# WX_sat_filter.net
KiCad netlist of a schematic drawn in Altium Designer
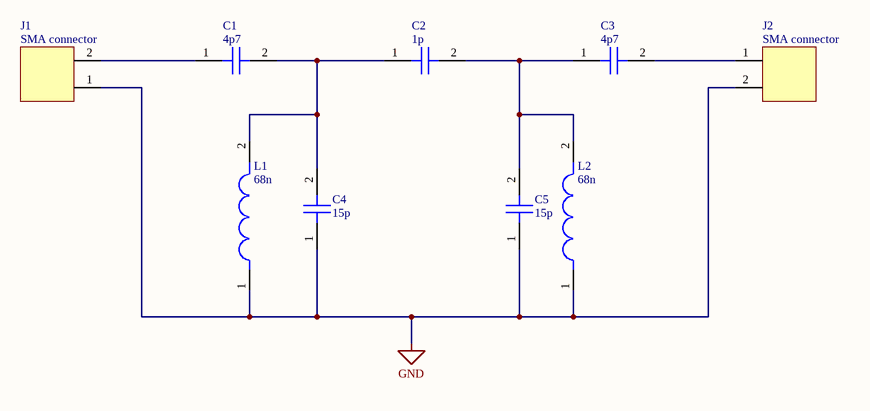
[diagram p0: WX sat filter.SchDoc]

(export (version "E")
  (design (tool "Eeschema 10.0.6"))
  (components
    (comp (ref "C1")
      (value "4p7")
      (footprint "0603_CAP")
      (libsource (lib "Radolovic_SCH_Library") (part "CAP_0603_generic"))
    )
    (comp (ref "C2")
      (value "1p")
      (footprint "0603_CAP")
      (libsource (lib "Radolovic_SCH_Library") (part "CAP_0603_generic"))
    )
    (comp (ref "C3")
      (value "4p7")
      (footprint "0603_CAP")
      (libsource (lib "Radolovic_SCH_Library") (part "CAP_0603_generic"))
    )
    (comp (ref "C4")
      (value "15p")
      (footprint "0603_CAP")
      (libsource (lib "Radolovic_SCH_Library") (part "CAP_0603_generic"))
    )
    (comp (ref "C5")
      (value "15p")
      (footprint "0603_CAP")
      (libsource (lib "Radolovic_SCH_Library") (part "CAP_0603_generic"))
    )
    (comp (ref "J1")
      (value "SMA connector")
      (libsource (lib "Radolovic_SCH_Library") (part "HEADER_1x2_0.254MM"))
    )
    (comp (ref "J2") (value "SMA connector") (libsource (lib "") (part "HEADER_1x2_0.254MM_1")))
    (comp (ref "L1")
      (value "68n")
      (footprint "0603_CAP")
      (libsource (lib "Radolovic_SCH_Library") (part "IND_air_0603_generic"))
    )
    (comp (ref "L2")
      (value "68n")
      (footprint "0603_CAP")
      (libsource (lib "Radolovic_SCH_Library") (part "IND_air_0603_generic"))
    )
  )
  (nets
    (net (code "1") (name "GND") (class "Default")
      (node (ref "C4") (pin "1") (pintype "passive"))
      (node (ref "C5") (pin "1") (pintype "passive"))
      (node (ref "J1") (pin "1") (pintype "passive"))
      (node (ref "J2") (pin "2") (pintype "passive"))
      (node (ref "L1") (pin "1") (pintype "passive"))
      (node (ref "L2") (pin "1") (pintype "passive"))
    )
    (net (code "2") (name "Net-(C1-Pad1)") (class "Default")
      (node (ref "C1") (pin "1") (pintype "passive"))
      (node (ref "J1") (pin "2") (pintype "passive"))
    )
    (net (code "3") (name "Net-(C1-Pad2)") (class "Default")
      (node (ref "C1") (pin "2") (pintype "passive"))
      (node (ref "C2") (pin "1") (pintype "passive"))
      (node (ref "C4") (pin "2") (pintype "passive"))
      (node (ref "L1") (pin "2") (pintype "passive"))
    )
    (net (code "4") (name "Net-(C2-Pad2)") (class "Default")
      (node (ref "C2") (pin "2") (pintype "passive"))
      (node (ref "C3") (pin "1") (pintype "passive"))
      (node (ref "C5") (pin "2") (pintype "passive"))
      (node (ref "L2") (pin "2") (pintype "passive"))
    )
    (net (code "5") (name "Net-(C3-Pad2)") (class "Default")
      (node (ref "C3") (pin "2") (pintype "passive"))
      (node (ref "J2") (pin "1") (pintype "passive"))
    )
  )
)
